# P06-Audio.net
KiCad netlist of a schematic drawn in Altium Designer
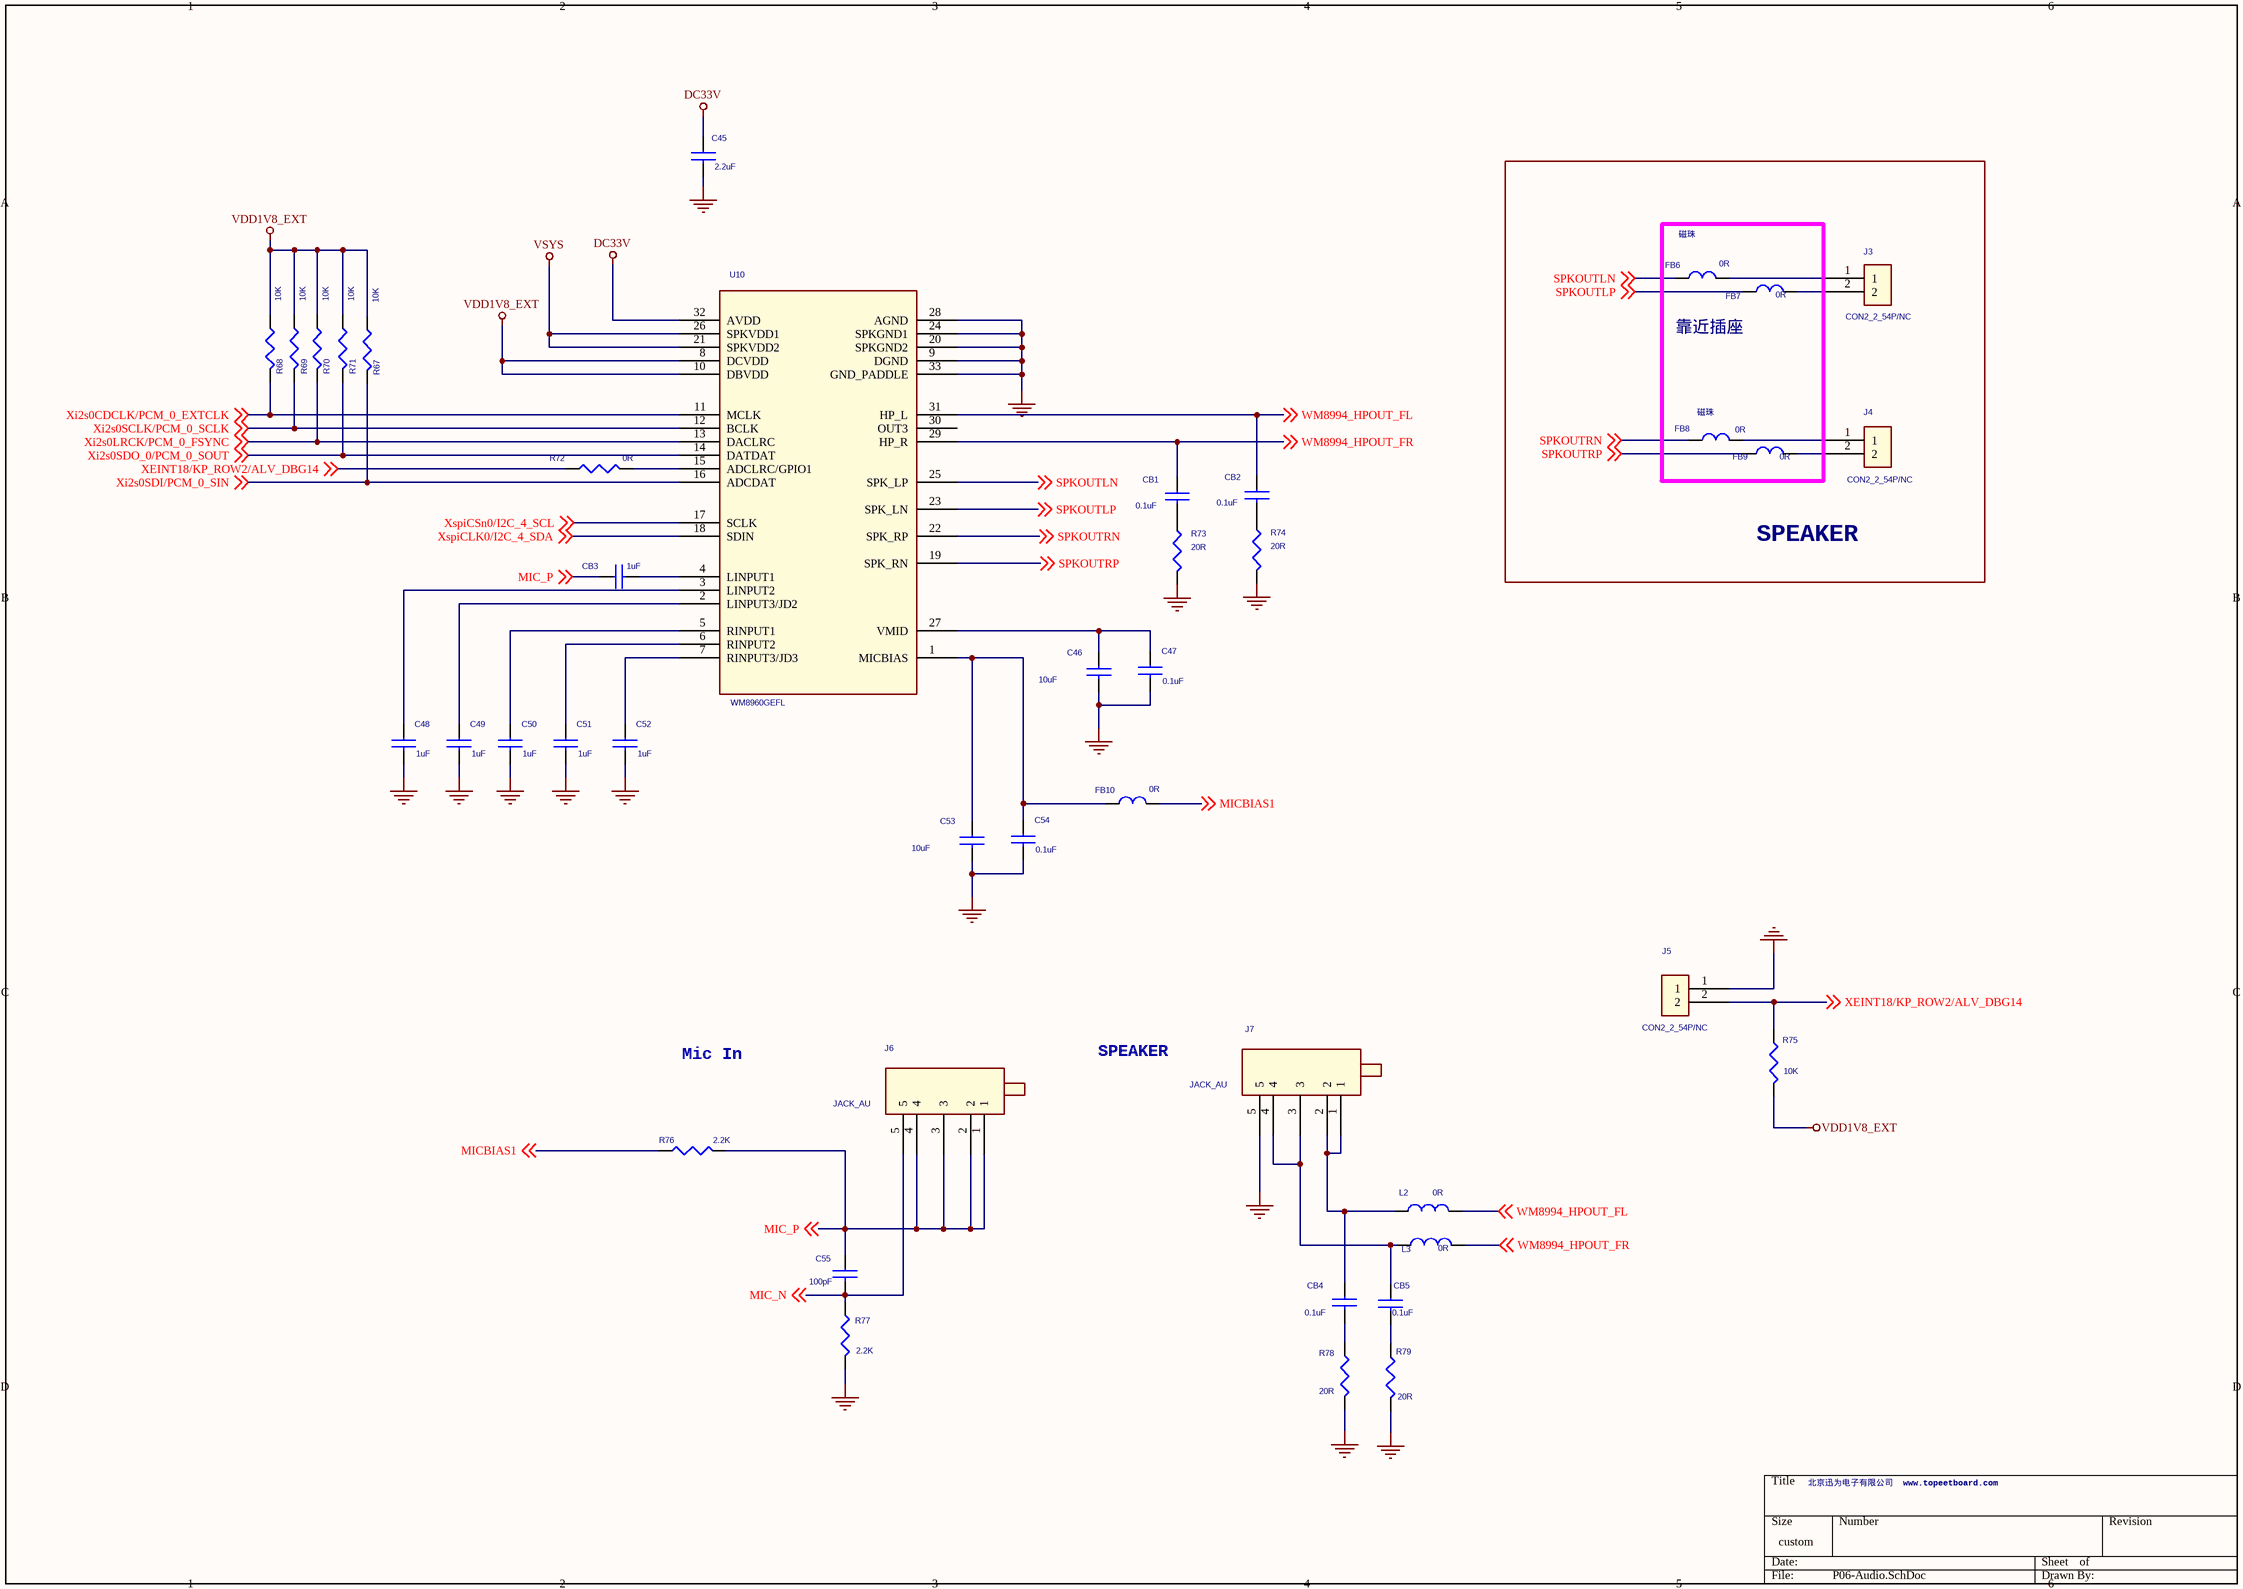
[diagram p0: P06-Audio.SchDoc]

(export (version "E")
  (design (tool "Eeschema 10.0.6"))
  (components
    (comp (ref "C45") (value "2.2uF") (footprint "C0603") (libsource (lib "*") (part "C0603_0")))
    (comp (ref "C46") (value "10uF") (footprint "C0603") (libsource (lib "*") (part "C0603_0")))
    (comp (ref "C47") (value "0.1uF") (footprint "C0603") (libsource (lib "*") (part "C0603_0")))
    (comp (ref "C48") (value "1uF") (footprint "C0603") (libsource (lib "*") (part "C0603_0")))
    (comp (ref "C49") (value "1uF") (footprint "C0603") (libsource (lib "*") (part "C0603_0")))
    (comp (ref "C50") (value "1uF") (footprint "C0603") (libsource (lib "*") (part "C0603_0")))
    (comp (ref "C51") (value "1uF") (footprint "C0603") (libsource (lib "*") (part "C0603_0")))
    (comp (ref "C52") (value "1uF") (footprint "C0603") (libsource (lib "*") (part "C0603_0")))
    (comp (ref "C53") (value "10uF") (footprint "C0603") (libsource (lib "*") (part "C0603_0")))
    (comp (ref "C54") (value "0.1uF") (footprint "C0603") (libsource (lib "*") (part "C0603_0")))
    (comp (ref "C55") (value "100pF") (footprint "C1608") (libsource (lib "*") (part "C1608")))
    (comp (ref "CB1") (value "0.1uF") (footprint "C1608") (libsource (lib "*") (part "C1608_Dup2")))
    (comp (ref "CB2") (value "0.1uF") (footprint "C1608") (libsource (lib "*") (part "C1608_Dup2")))
    (comp (ref "CB3") (value "1uF") (footprint "C1608") (libsource (lib "*") (part "C1608_Dup2")))
    (comp (ref "CB4") (value "0.1uF") (footprint "C1608") (libsource (lib "*") (part "C1608_Dup2")))
    (comp (ref "CB5") (value "0.1uF") (footprint "C1608") (libsource (lib "*") (part "C1608_Dup2")))
    (comp (ref "FB6") (value "0R") (footprint "1206-A") (libsource (lib "*") (part "FB1206_0")))
    (comp (ref "FB7") (value "0R") (footprint "1206-A") (libsource (lib "*") (part "FB1206_0")))
    (comp (ref "FB8") (value "0R") (footprint "1206-A") (libsource (lib "*") (part "FB1206_0")))
    (comp (ref "FB9") (value "0R") (footprint "1206-A") (libsource (lib "*") (part "FB1206_0")))
    (comp (ref "FB10") (value "0R") (footprint "1206-A") (libsource (lib "*") (part "FB1206_0")))
    (comp (ref "J3") (value "CON2_2_54P/NC") (libsource (lib "*") (part "CON2_2_54P")))
    (comp (ref "J4") (value "CON2_2_54P/NC") (libsource (lib "*") (part "CON2_2_54P")))
    (comp (ref "J5") (value "CON2_2_54P/NC") (libsource (lib "*") (part "CON2-2_54P")))
    (comp (ref "J6") (value "JACK_AU") (libsource (lib "*") (part "JACK_AU")))
    (comp (ref "J7") (value "JACK_AU") (libsource (lib "*") (part "JACK_AU")))
    (comp (ref "L2") (value "0R") (footprint "LQH32C") (libsource (lib "*") (part "LQH32C_0_Dup1")))
    (comp (ref "L3") (value "0R") (footprint "LQH32C") (libsource (lib "*") (part "LQH32C_0_Dup1")))
    (comp (ref "R67") (value "10K") (libsource (lib "*") (part "R_Dup1")))
    (comp (ref "R68") (value "10K") (libsource (lib "*") (part "R_Dup1")))
    (comp (ref "R69") (value "10K") (libsource (lib "*") (part "R_Dup1")))
    (comp (ref "R70") (value "10K") (libsource (lib "*") (part "R_Dup1")))
    (comp (ref "R71") (value "10K") (libsource (lib "*") (part "R_Dup1")))
    (comp (ref "R72") (value "0R") (libsource (lib "*") (part "R_Dup1")))
    (comp (ref "R73") (value "20R") (footprint "R1005") (libsource (lib "*") (part "R1005_0")))
    (comp (ref "R74") (value "20R") (footprint "R1005") (libsource (lib "*") (part "R1005_0")))
    (comp (ref "R75") (value "10K") (footprint "R1005") (libsource (lib "*") (part "R1005_0")))
    (comp (ref "R76") (value "2.2K") (footprint "R1005") (libsource (lib "*") (part "R1005_0")))
    (comp (ref "R77") (value "2.2K") (footprint "R1005") (libsource (lib "*") (part "R1005_0")))
    (comp (ref "R78") (value "20R") (footprint "R1005") (libsource (lib "*") (part "R1005_0")))
    (comp (ref "R79") (value "20R") (footprint "R1005") (libsource (lib "*") (part "R1005_0")))
    (comp (ref "U10") (value "WM8960GEFL") (libsource (lib "*") (part "WM8960GEFL_0")))
  )
  (nets
    (net (code "1") (name "DC33V") (class "Default")
      (node (ref "C45") (pin "1") (pinfunction "1_1") (pintype "passive"))
      (node (ref "U10") (pin "32") (pinfunction "AVDD_32") (pintype "passive"))
    )
    (net (code "2") (name "GND") (class "Default")
      (node (ref "C45") (pin "2") (pinfunction "2_2") (pintype "passive"))
      (node (ref "C46") (pin "2") (pinfunction "2_2") (pintype "passive"))
      (node (ref "C47") (pin "2") (pinfunction "2_2") (pintype "passive"))
      (node (ref "C48") (pin "2") (pinfunction "2_2") (pintype "passive"))
      (node (ref "C49") (pin "2") (pinfunction "2_2") (pintype "passive"))
      (node (ref "C50") (pin "2") (pinfunction "2_2") (pintype "passive"))
      (node (ref "C51") (pin "2") (pinfunction "2_2") (pintype "passive"))
      (node (ref "C52") (pin "2") (pinfunction "2_2") (pintype "passive"))
      (node (ref "C53") (pin "2") (pinfunction "2_2") (pintype "passive"))
      (node (ref "C54") (pin "2") (pinfunction "2_2") (pintype "passive"))
      (node (ref "J5") (pin "1") (pinfunction "1_1") (pintype "passive"))
      (node (ref "J7") (pin "5") (pinfunction "5_5") (pintype "passive"))
      (node (ref "R73") (pin "2") (pinfunction "2_2") (pintype "passive"))
      (node (ref "R74") (pin "2") (pinfunction "2_2") (pintype "passive"))
      (node (ref "R77") (pin "2") (pinfunction "2_2") (pintype "passive"))
      (node (ref "R78") (pin "2") (pinfunction "2_2") (pintype "passive"))
      (node (ref "R79") (pin "2") (pinfunction "2_2") (pintype "passive"))
      (node (ref "U10") (pin "20") (pinfunction "SPKGND2_20") (pintype "passive"))
      (node (ref "U10") (pin "24") (pinfunction "SPKGND1_24") (pintype "passive"))
      (node (ref "U10") (pin "28") (pinfunction "AGND_28") (pintype "passive"))
      (node (ref "U10") (pin "33") (pinfunction "GND_PADDLE_33") (pintype "passive"))
      (node (ref "U10") (pin "9") (pinfunction "DGND_9") (pintype "passive"))
    )
    (net (code "3") (name "MICBIAS1") (class "Default")
      (node (ref "FB10") (pin "2") (pinfunction "2_2") (pintype "passive"))
      (node (ref "R76") (pin "1") (pinfunction "1_1") (pintype "passive"))
    )
    (net (code "4") (name "MIC_N") (class "Default")
      (node (ref "C55") (pin "2") (pinfunction "2_2") (pintype "passive"))
      (node (ref "J6") (pin "5") (pinfunction "5_5") (pintype "passive"))
      (node (ref "R77") (pin "1") (pinfunction "1_1") (pintype "passive"))
    )
    (net (code "5") (name "MIC_P") (class "Default")
      (node (ref "C55") (pin "1") (pinfunction "1_1") (pintype "passive"))
      (node (ref "CB3") (pin "1") (pinfunction "1_1") (pintype "passive"))
      (node (ref "J6") (pin "1") (pinfunction "1_1") (pintype "passive"))
      (node (ref "J6") (pin "2") (pinfunction "2_2") (pintype "passive"))
      (node (ref "J6") (pin "3") (pinfunction "3_3") (pintype "passive"))
      (node (ref "J6") (pin "4") (pinfunction "4_4") (pintype "passive"))
      (node (ref "R76") (pin "2") (pinfunction "2_2") (pintype "passive"))
    )
    (net (code "6") (name "Net-(CB1-Pad2)") (class "Default")
      (node (ref "CB1") (pin "2") (pinfunction "2_2") (pintype "passive"))
      (node (ref "R73") (pin "1") (pinfunction "1_1") (pintype "passive"))
    )
    (net (code "7") (name "Net-(CB2-Pad2)") (class "Default")
      (node (ref "CB2") (pin "2") (pinfunction "2_2") (pintype "passive"))
      (node (ref "R74") (pin "1") (pinfunction "1_1") (pintype "passive"))
    )
    (net (code "8") (name "Net-(CB4-Pad1)") (class "Default")
      (node (ref "CB4") (pin "1") (pinfunction "1_1") (pintype "passive"))
      (node (ref "J7") (pin "1") (pinfunction "1_1") (pintype "passive"))
      (node (ref "J7") (pin "2") (pinfunction "2_2") (pintype "passive"))
      (node (ref "L2") (pin "1") (pinfunction "1_1") (pintype "passive"))
    )
    (net (code "9") (name "Net-(CB4-Pad2)") (class "Default")
      (node (ref "CB4") (pin "2") (pinfunction "2_2") (pintype "passive"))
      (node (ref "R78") (pin "1") (pinfunction "1_1") (pintype "passive"))
    )
    (net (code "10") (name "Net-(CB5-Pad1)") (class "Default")
      (node (ref "CB5") (pin "1") (pinfunction "1_1") (pintype "passive"))
      (node (ref "J7") (pin "3") (pinfunction "3_3") (pintype "passive"))
      (node (ref "J7") (pin "4") (pinfunction "4_4") (pintype "passive"))
      (node (ref "L3") (pin "1") (pinfunction "1_1") (pintype "passive"))
    )
    (net (code "11") (name "Net-(CB5-Pad2)") (class "Default")
      (node (ref "CB5") (pin "2") (pinfunction "2_2") (pintype "passive"))
      (node (ref "R79") (pin "1") (pinfunction "1_1") (pintype "passive"))
    )
    (net (code "12") (name "Net-(FB6-Pad2)") (class "Default")
      (node (ref "FB6") (pin "2") (pinfunction "2_2") (pintype "passive"))
      (node (ref "J3") (pin "1") (pinfunction "1_1") (pintype "passive"))
    )
    (net (code "13") (name "Net-(FB7-Pad2)") (class "Default")
      (node (ref "FB7") (pin "2") (pinfunction "2_2") (pintype "passive"))
      (node (ref "J3") (pin "2") (pinfunction "2_2") (pintype "passive"))
    )
    (net (code "14") (name "Net-(FB8-Pad2)") (class "Default")
      (node (ref "FB8") (pin "2") (pinfunction "2_2") (pintype "passive"))
      (node (ref "J4") (pin "1") (pinfunction "1_1") (pintype "passive"))
    )
    (net (code "15") (name "Net-(FB9-Pad2)") (class "Default")
      (node (ref "FB9") (pin "2") (pinfunction "2_2") (pintype "passive"))
      (node (ref "J4") (pin "2") (pinfunction "2_2") (pintype "passive"))
    )
    (net (code "16") (name "Net-(U10-ADCLRC{slash}GPIO1)") (class "Default")
      (node (ref "R72") (pin "2") (pinfunction "2_2") (pintype "passive"))
      (node (ref "U10") (pin "15") (pinfunction "ADCLRC/GPIO1_15") (pintype "passive"))
    )
    (net (code "17") (name "Net-(U10-LINPUT1)") (class "Default")
      (node (ref "CB3") (pin "2") (pinfunction "2_2") (pintype "passive"))
      (node (ref "U10") (pin "4") (pinfunction "LINPUT1_4") (pintype "passive"))
    )
    (net (code "18") (name "Net-(U10-LINPUT2)") (class "Default")
      (node (ref "C48") (pin "1") (pinfunction "1_1") (pintype "passive"))
      (node (ref "U10") (pin "3") (pinfunction "LINPUT2_3") (pintype "passive"))
    )
    (net (code "19") (name "Net-(U10-LINPUT3{slash}JD2)") (class "Default")
      (node (ref "C49") (pin "1") (pinfunction "1_1") (pintype "passive"))
      (node (ref "U10") (pin "2") (pinfunction "LINPUT3/JD2_2") (pintype "passive"))
    )
    (net (code "20") (name "Net-(U10-MICBIAS)") (class "Default")
      (node (ref "C53") (pin "1") (pinfunction "1_1") (pintype "passive"))
      (node (ref "C54") (pin "1") (pinfunction "1_1") (pintype "passive"))
      (node (ref "FB10") (pin "1") (pinfunction "1_1") (pintype "passive"))
      (node (ref "U10") (pin "1") (pinfunction "MICBIAS_1") (pintype "passive"))
    )
    (net (code "21") (name "Net-(U10-RINPUT1)") (class "Default")
      (node (ref "C50") (pin "1") (pinfunction "1_1") (pintype "passive"))
      (node (ref "U10") (pin "5") (pinfunction "RINPUT1_5") (pintype "passive"))
    )
    (net (code "22") (name "Net-(U10-RINPUT2)") (class "Default")
      (node (ref "C51") (pin "1") (pinfunction "1_1") (pintype "passive"))
      (node (ref "U10") (pin "6") (pinfunction "RINPUT2_6") (pintype "passive"))
    )
    (net (code "23") (name "Net-(U10-RINPUT3{slash}JD3)") (class "Default")
      (node (ref "C52") (pin "1") (pinfunction "1_1") (pintype "passive"))
      (node (ref "U10") (pin "7") (pinfunction "RINPUT3/JD3_7") (pintype "passive"))
    )
    (net (code "24") (name "Net-(U10-VMID)") (class "Default")
      (node (ref "C46") (pin "1") (pinfunction "1_1") (pintype "passive"))
      (node (ref "C47") (pin "1") (pinfunction "1_1") (pintype "passive"))
      (node (ref "U10") (pin "27") (pinfunction "VMID_27") (pintype "passive"))
    )
    (net (code "25") (name "SPKOUTLN") (class "Default")
      (node (ref "FB6") (pin "1") (pinfunction "1_1") (pintype "passive"))
      (node (ref "U10") (pin "25") (pinfunction "SPK_LP_25") (pintype "passive"))
    )
    (net (code "26") (name "SPKOUTLP") (class "Default")
      (node (ref "FB7") (pin "1") (pinfunction "1_1") (pintype "passive"))
      (node (ref "U10") (pin "23") (pinfunction "SPK_LN_23") (pintype "passive"))
    )
    (net (code "27") (name "SPKOUTRN") (class "Default")
      (node (ref "FB8") (pin "1") (pinfunction "1_1") (pintype "passive"))
      (node (ref "U10") (pin "22") (pinfunction "SPK_RP_22") (pintype "passive"))
    )
    (net (code "28") (name "SPKOUTRP") (class "Default")
      (node (ref "FB9") (pin "1") (pinfunction "1_1") (pintype "passive"))
      (node (ref "U10") (pin "19") (pinfunction "SPK_RN_19") (pintype "passive"))
    )
    (net (code "29") (name "VDD1V8_EXT") (class "Default")
      (node (ref "R67") (pin "1") (pinfunction "1_1") (pintype "passive"))
      (node (ref "R68") (pin "1") (pinfunction "1_1") (pintype "passive"))
      (node (ref "R69") (pin "1") (pinfunction "1_1") (pintype "passive"))
      (node (ref "R70") (pin "1") (pinfunction "1_1") (pintype "passive"))
      (node (ref "R71") (pin "1") (pinfunction "1_1") (pintype "passive"))
      (node (ref "R75") (pin "2") (pinfunction "2_2") (pintype "passive"))
      (node (ref "U10") (pin "10") (pinfunction "DBVDD_10") (pintype "passive"))
      (node (ref "U10") (pin "8") (pinfunction "DCVDD_8") (pintype "passive"))
    )
    (net (code "30") (name "VSYS") (class "Default")
      (node (ref "U10") (pin "21") (pinfunction "SPKVDD2_21") (pintype "passive"))
      (node (ref "U10") (pin "26") (pinfunction "SPKVDD1_26") (pintype "passive"))
    )
    (net (code "31") (name "WM8994_HPOUT_FL") (class "Default")
      (node (ref "CB2") (pin "1") (pinfunction "1_1") (pintype "passive"))
      (node (ref "L2") (pin "2") (pinfunction "2_2") (pintype "passive"))
      (node (ref "U10") (pin "31") (pinfunction "HP_L_31") (pintype "passive"))
    )
    (net (code "32") (name "WM8994_HPOUT_FR") (class "Default")
      (node (ref "CB1") (pin "1") (pinfunction "1_1") (pintype "passive"))
      (node (ref "L3") (pin "2") (pinfunction "2_2") (pintype "passive"))
      (node (ref "U10") (pin "29") (pinfunction "HP_R_29") (pintype "passive"))
    )
    (net (code "33") (name "XEINT18{slash}KP_ROW2{slash}ALV_DBG14") (class "Default")
      (node (ref "J5") (pin "2") (pinfunction "2_2") (pintype "passive"))
      (node (ref "R72") (pin "1") (pinfunction "1_1") (pintype "passive"))
      (node (ref "R75") (pin "1") (pinfunction "1_1") (pintype "passive"))
    )
    (net (code "34") (name "Xi2s0CDCLK{slash}PCM_0_EXTCLK") (class "Default")
      (node (ref "R68") (pin "2") (pinfunction "2_2") (pintype "passive"))
      (node (ref "U10") (pin "11") (pinfunction "MCLK_11") (pintype "passive"))
    )
    (net (code "35") (name "Xi2s0LRCK{slash}PCM_0_FSYNC") (class "Default")
      (node (ref "R70") (pin "2") (pinfunction "2_2") (pintype "passive"))
      (node (ref "U10") (pin "13") (pinfunction "DACLRC_13") (pintype "passive"))
    )
    (net (code "36") (name "Xi2s0SCLK{slash}PCM_0_SCLK") (class "Default")
      (node (ref "R69") (pin "2") (pinfunction "2_2") (pintype "passive"))
      (node (ref "U10") (pin "12") (pinfunction "BCLK_12") (pintype "passive"))
    )
    (net (code "37") (name "Xi2s0SDI{slash}PCM_0_SIN") (class "Default")
      (node (ref "R67") (pin "2") (pinfunction "2_2") (pintype "passive"))
      (node (ref "U10") (pin "16") (pinfunction "ADCDAT_16") (pintype "passive"))
    )
    (net (code "38") (name "Xi2s0SDO_0{slash}PCM_0_SOUT") (class "Default")
      (node (ref "R71") (pin "2") (pinfunction "2_2") (pintype "passive"))
      (node (ref "U10") (pin "14") (pinfunction "DATDAT_14") (pintype "passive"))
    )
    (net (code "39") (name "XspiCLK0{slash}I2C_4_SDA") (class "Default")
      (node (ref "U10") (pin "18") (pinfunction "SDIN_18") (pintype "passive"))
    )
    (net (code "40") (name "XspiCSn0{slash}I2C_4_SCL") (class "Default")
      (node (ref "U10") (pin "17") (pinfunction "SCLK_17") (pintype "passive"))
    )
    (net (code "41") (name "unconnected-(U10-OUT3-Pad30)") (class "Default")
      (node (ref "U10") (pin "30") (pinfunction "OUT3_30") (pintype "passive"))
    )
  )
)
